# Aux_Power_Board_V2.net
KiCad netlist of a schematic drawn in EAGLE
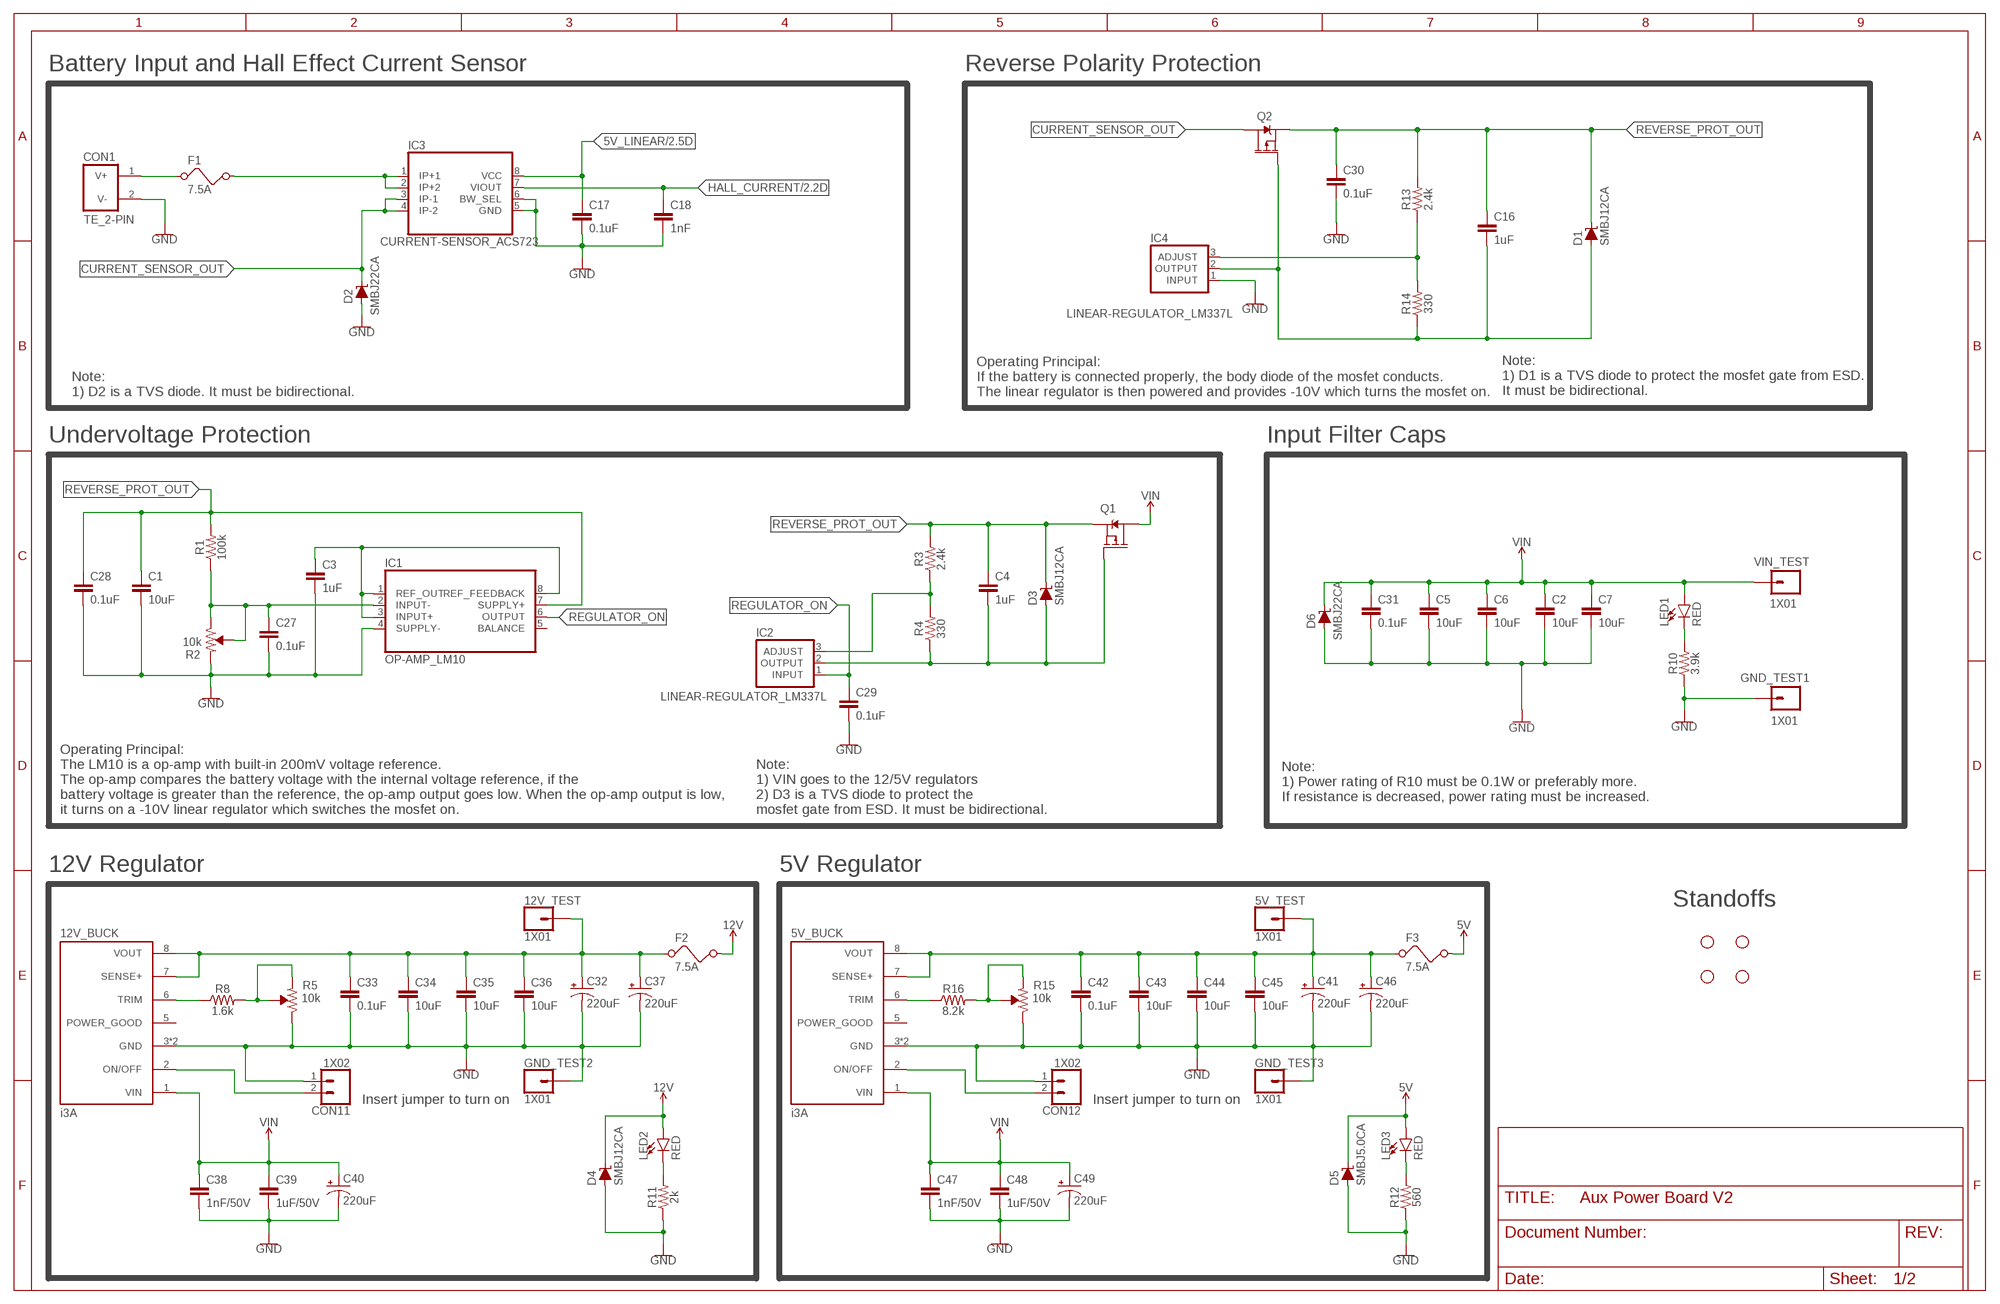
[diagram p0: schematic, sheet 1]
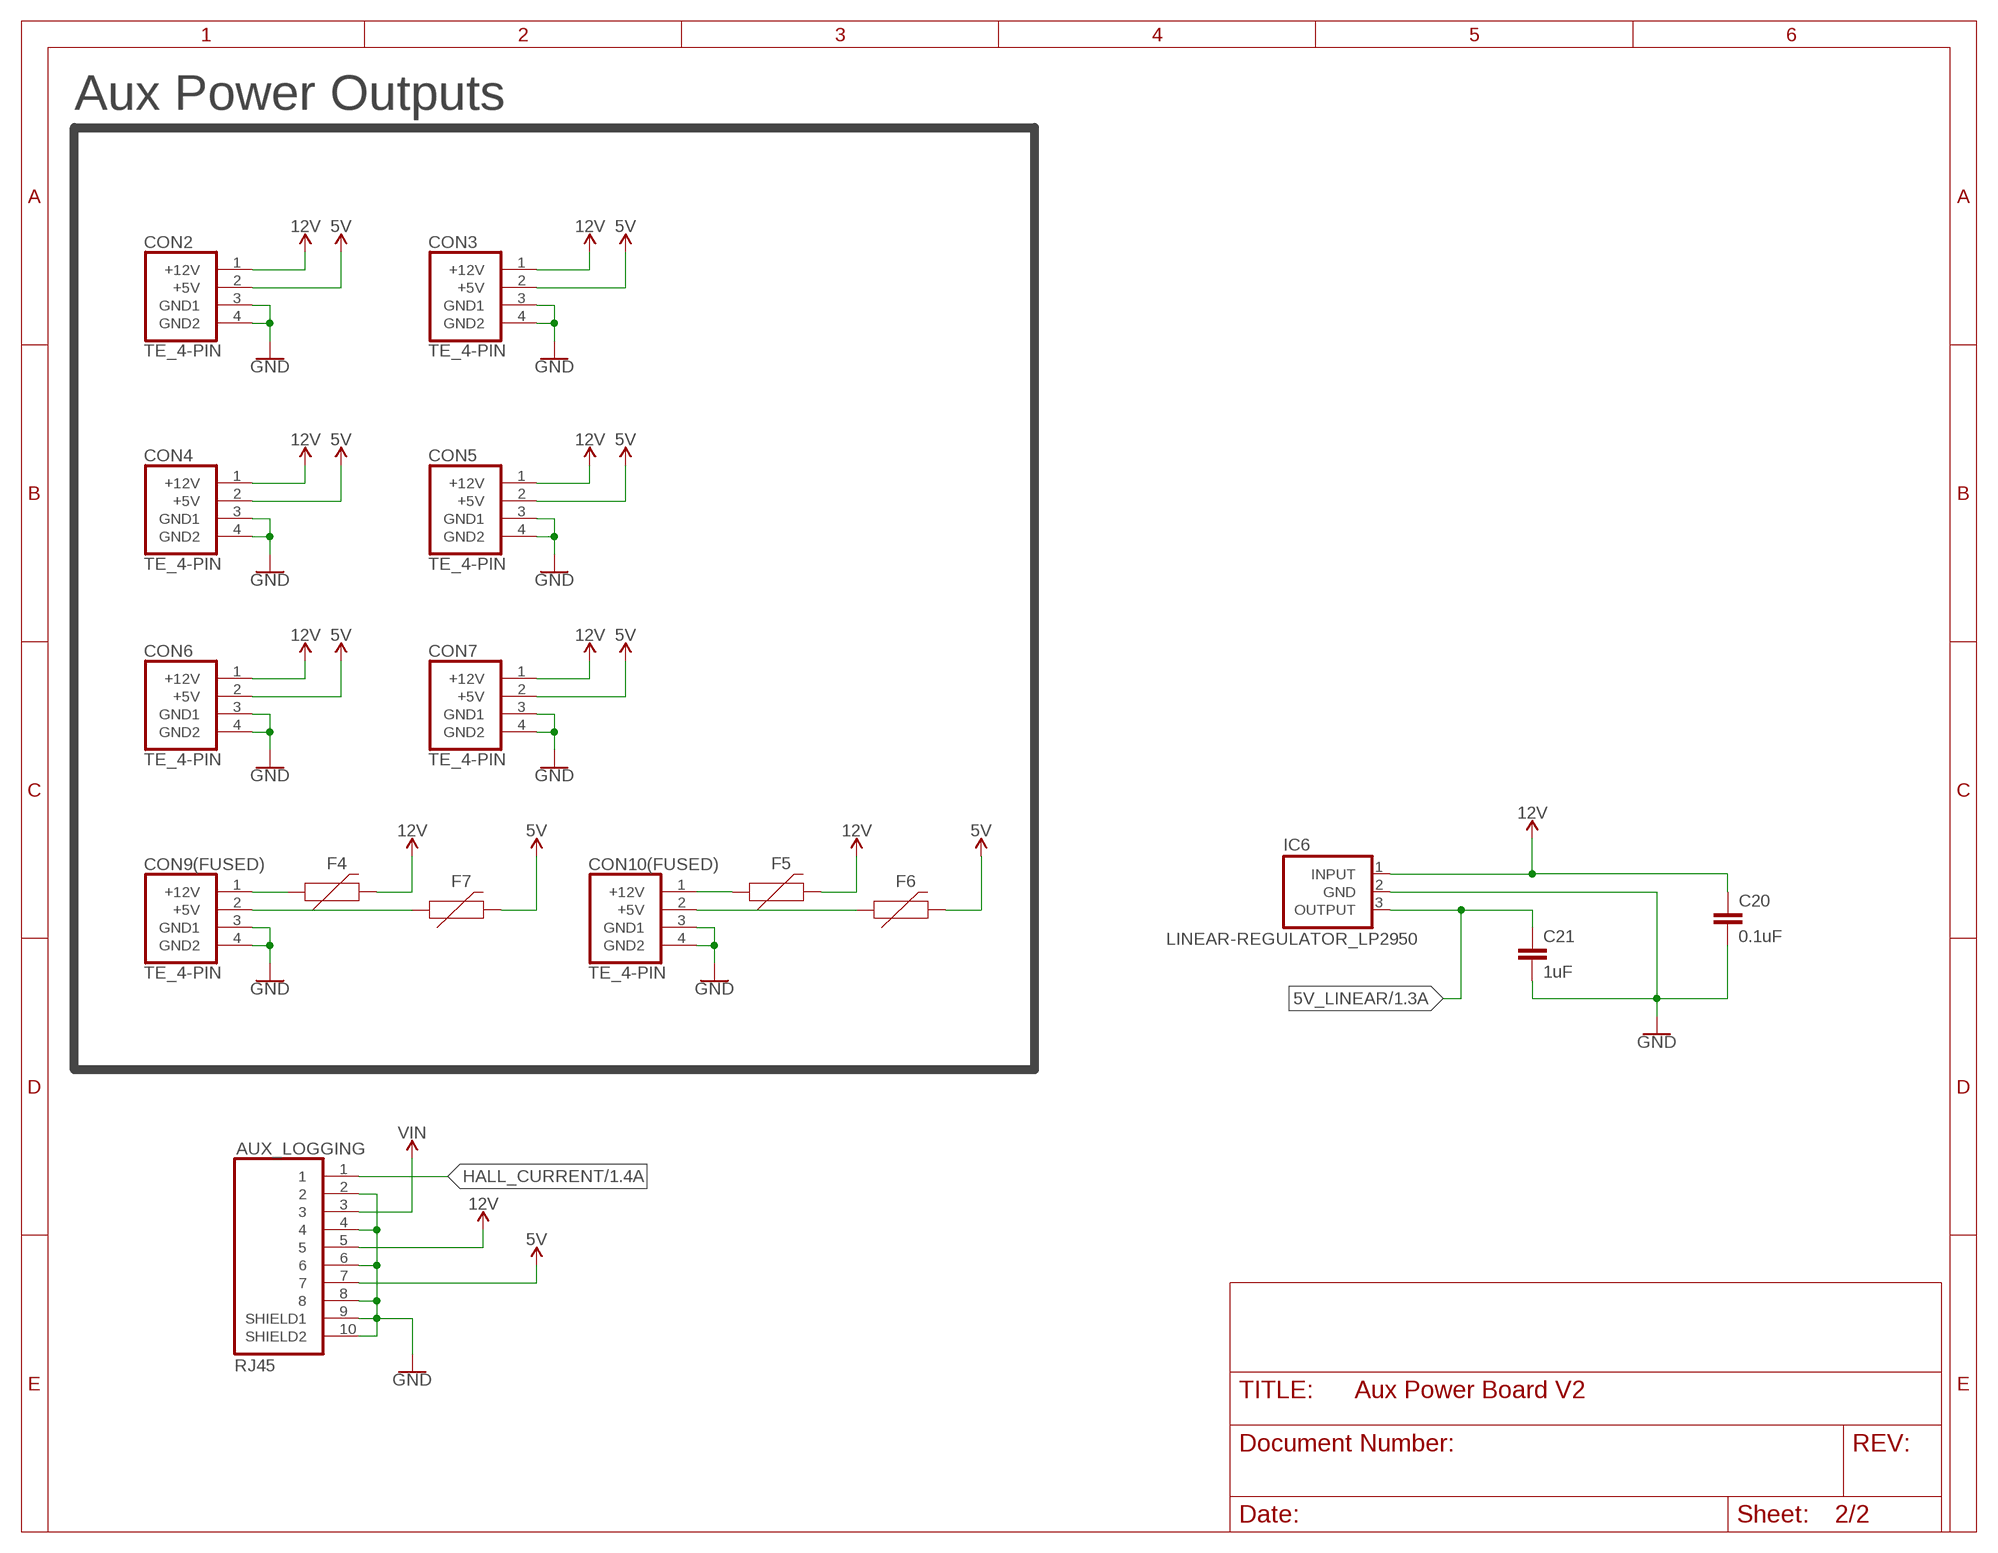
[diagram p1: schematic, sheet 2]

(export (version "E")
  (design (tool "Eeschema 10.0.6"))
  (components
    (comp (ref "AUX_LOGGING")
      (value "RJ45")
      (footprint "eagle-import:RJ45")
      (libsource (lib "eagle-import") (part "RJ45"))
    )
    (comp (ref "C20")
      (value "0.1uF")
      (footprint "eagle-import:0805")
      (libsource (lib "eagle-import") (part "CAPACITOR_0805"))
    )
    (comp (ref "C21")
      (value "1uF")
      (footprint "eagle-import:0805")
      (libsource (lib "eagle-import") (part "CAPACITOR_0805"))
    )
    (comp (ref "CON2")
      (value "TE_4-PIN")
      (footprint "eagle-import:TE_4-PIN")
      (libsource (lib "eagle-import") (part "TE_4-PIN"))
    )
    (comp (ref "CON3")
      (value "TE_4-PIN")
      (footprint "eagle-import:TE_4-PIN")
      (libsource (lib "eagle-import") (part "TE_4-PIN"))
    )
    (comp (ref "CON4")
      (value "TE_4-PIN")
      (footprint "eagle-import:TE_4-PIN")
      (libsource (lib "eagle-import") (part "TE_4-PIN"))
    )
    (comp (ref "CON5")
      (value "TE_4-PIN")
      (footprint "eagle-import:TE_4-PIN")
      (libsource (lib "eagle-import") (part "TE_4-PIN"))
    )
    (comp (ref "CON6")
      (value "TE_4-PIN")
      (footprint "eagle-import:TE_4-PIN")
      (libsource (lib "eagle-import") (part "TE_4-PIN"))
    )
    (comp (ref "CON7")
      (value "TE_4-PIN")
      (footprint "eagle-import:TE_4-PIN")
      (libsource (lib "eagle-import") (part "TE_4-PIN"))
    )
    (comp (ref "CON9(FUSED)")
      (value "TE_4-PIN")
      (footprint "eagle-import:TE_4-PIN")
      (libsource (lib "eagle-import") (part "TE_4-PIN"))
    )
    (comp (ref "CON10(FUSED)")
      (value "TE_4-PIN")
      (footprint "eagle-import:TE_4-PIN")
      (libsource (lib "eagle-import") (part "TE_4-PIN"))
    )
    (comp (ref "F4")
      (value "FUSE_1210_RESETTABLE")
      (footprint "eagle-import:1210")
      (libsource (lib "eagle-import") (part "FUSE_1210_RESETTABLE"))
    )
    (comp (ref "F5")
      (value "FUSE_1210_RESETTABLE")
      (footprint "eagle-import:1210")
      (libsource (lib "eagle-import") (part "FUSE_1210_RESETTABLE"))
    )
    (comp (ref "F6")
      (value "FUSE_1210_RESETTABLE")
      (footprint "eagle-import:1210")
      (libsource (lib "eagle-import") (part "FUSE_1210_RESETTABLE"))
    )
    (comp (ref "F7")
      (value "FUSE_1210_RESETTABLE")
      (footprint "eagle-import:1210")
      (libsource (lib "eagle-import") (part "FUSE_1210_RESETTABLE"))
    )
    (comp (ref "IC6")
      (value "LINEAR-REGULATOR_LP2950")
      (footprint "eagle-import:TO92")
      (libsource (lib "eagle-import") (part "LINEAR-REGULATOR_LP2950"))
    )
    (comp (ref "5V_BUCK")
      (value "i3A")
      (footprint "eagle-import:CONVERTER_I3A")
      (libsource (lib "eagle-import") (part "CONVERTER_I3A"))
    )
    (comp (ref "5V_TEST")
      (value "1X01")
      (footprint "eagle-import:1X01")
      (libsource (lib "eagle-import") (part "1X01"))
    )
    (comp (ref "12V_BUCK")
      (value "i3A")
      (footprint "eagle-import:CONVERTER_I3A")
      (libsource (lib "eagle-import") (part "CONVERTER_I3A"))
    )
    (comp (ref "12V_TEST")
      (value "1X01")
      (footprint "eagle-import:1X01")
      (libsource (lib "eagle-import") (part "1X01"))
    )
    (comp (ref "C1")
      (value "10uF")
      (footprint "eagle-import:1210")
      (libsource (lib "eagle-import") (part "CAPACITOR_1210"))
    )
    (comp (ref "C2")
      (value "10uF")
      (footprint "eagle-import:1210")
      (libsource (lib "eagle-import") (part "CAPACITOR_1210"))
    )
    (comp (ref "C3")
      (value "1uF")
      (footprint "eagle-import:0805")
      (libsource (lib "eagle-import") (part "CAPACITOR_0805"))
    )
    (comp (ref "C4")
      (value "1uF")
      (footprint "eagle-import:0805")
      (libsource (lib "eagle-import") (part "CAPACITOR_0805"))
    )
    (comp (ref "C5")
      (value "10uF")
      (footprint "eagle-import:1210")
      (libsource (lib "eagle-import") (part "CAPACITOR_1210"))
    )
    (comp (ref "C6")
      (value "10uF")
      (footprint "eagle-import:1210")
      (libsource (lib "eagle-import") (part "CAPACITOR_1210"))
    )
    (comp (ref "C7")
      (value "10uF")
      (footprint "eagle-import:1210")
      (libsource (lib "eagle-import") (part "CAPACITOR_1210"))
    )
    (comp (ref "C16")
      (value "1uF")
      (footprint "eagle-import:0805")
      (libsource (lib "eagle-import") (part "CAPACITOR_0805"))
    )
    (comp (ref "C17")
      (value "0.1uF")
      (footprint "eagle-import:0805")
      (libsource (lib "eagle-import") (part "CAPACITOR_0805"))
    )
    (comp (ref "C18")
      (value "1nF")
      (footprint "eagle-import:0805")
      (libsource (lib "eagle-import") (part "CAPACITOR_0805"))
    )
    (comp (ref "C27")
      (value "0.1uF")
      (footprint "eagle-import:0805")
      (libsource (lib "eagle-import") (part "CAPACITOR_0805"))
    )
    (comp (ref "C28")
      (value "0.1uF")
      (footprint "eagle-import:0805")
      (libsource (lib "eagle-import") (part "CAPACITOR_0805"))
    )
    (comp (ref "C29")
      (value "0.1uF")
      (footprint "eagle-import:0805")
      (libsource (lib "eagle-import") (part "CAPACITOR_0805"))
    )
    (comp (ref "C30")
      (value "0.1uF")
      (footprint "eagle-import:0805")
      (libsource (lib "eagle-import") (part "CAPACITOR_0805"))
    )
    (comp (ref "C31")
      (value "0.1uF")
      (footprint "eagle-import:0805")
      (libsource (lib "eagle-import") (part "CAPACITOR_0805"))
    )
    (comp (ref "C32")
      (value "220uF")
      (footprint "eagle-import:CAPACITOR_220UF_63V")
      (libsource (lib "eagle-import") (part "CAPACITOR_ELECTROLYTIC_220UF"))
    )
    (comp (ref "C33")
      (value "0.1uF")
      (footprint "eagle-import:0805")
      (libsource (lib "eagle-import") (part "CAPACITOR_0805"))
    )
    (comp (ref "C34")
      (value "10uF")
      (footprint "eagle-import:0805")
      (libsource (lib "eagle-import") (part "CAPACITOR_0805"))
    )
    (comp (ref "C35")
      (value "10uF")
      (footprint "eagle-import:0805")
      (libsource (lib "eagle-import") (part "CAPACITOR_0805"))
    )
    (comp (ref "C36")
      (value "10uF")
      (footprint "eagle-import:0805")
      (libsource (lib "eagle-import") (part "CAPACITOR_0805"))
    )
    (comp (ref "C37")
      (value "220uF")
      (footprint "eagle-import:CAPACITOR_220UF_63V")
      (libsource (lib "eagle-import") (part "CAPACITOR_ELECTROLYTIC_220UF"))
    )
    (comp (ref "C38")
      (value "1nF/50V")
      (footprint "eagle-import:0805")
      (libsource (lib "eagle-import") (part "CAPACITOR_0805"))
    )
    (comp (ref "C39")
      (value "1uF/50V")
      (footprint "eagle-import:0805")
      (libsource (lib "eagle-import") (part "CAPACITOR_0805"))
    )
    (comp (ref "C40")
      (value "220uF")
      (footprint "eagle-import:CAPACITOR_220UF_63V")
      (libsource (lib "eagle-import") (part "CAPACITOR_ELECTROLYTIC_220UF"))
    )
    (comp (ref "C41")
      (value "220uF")
      (footprint "eagle-import:CAPACITOR_220UF_63V")
      (libsource (lib "eagle-import") (part "CAPACITOR_ELECTROLYTIC_220UF"))
    )
    (comp (ref "C42")
      (value "0.1uF")
      (footprint "eagle-import:0805")
      (libsource (lib "eagle-import") (part "CAPACITOR_0805"))
    )
    (comp (ref "C43")
      (value "10uF")
      (footprint "eagle-import:0805")
      (libsource (lib "eagle-import") (part "CAPACITOR_0805"))
    )
    (comp (ref "C44")
      (value "10uF")
      (footprint "eagle-import:0805")
      (libsource (lib "eagle-import") (part "CAPACITOR_0805"))
    )
    (comp (ref "C45")
      (value "10uF")
      (footprint "eagle-import:0805")
      (libsource (lib "eagle-import") (part "CAPACITOR_0805"))
    )
    (comp (ref "C46")
      (value "220uF")
      (footprint "eagle-import:CAPACITOR_220UF_63V")
      (libsource (lib "eagle-import") (part "CAPACITOR_ELECTROLYTIC_220UF"))
    )
    (comp (ref "C47")
      (value "1nF/50V")
      (footprint "eagle-import:0805")
      (libsource (lib "eagle-import") (part "CAPACITOR_0805"))
    )
    (comp (ref "C48")
      (value "1uF/50V")
      (footprint "eagle-import:0805")
      (libsource (lib "eagle-import") (part "CAPACITOR_0805"))
    )
    (comp (ref "C49")
      (value "220uF")
      (footprint "eagle-import:CAPACITOR_220UF_63V")
      (libsource (lib "eagle-import") (part "CAPACITOR_ELECTROLYTIC_220UF"))
    )
    (comp (ref "CON1")
      (value "TE_2-PIN")
      (footprint "eagle-import:TE_2-PIN")
      (libsource (lib "eagle-import") (part "TE_2-PIN"))
    )
    (comp (ref "CON11")
      (value "1X02")
      (footprint "eagle-import:1X02")
      (libsource (lib "eagle-import") (part "1X02"))
    )
    (comp (ref "CON12")
      (value "1X02")
      (footprint "eagle-import:1X02")
      (libsource (lib "eagle-import") (part "1X02"))
    )
    (comp (ref "D1")
      (value "SMBJ12CA")
      (footprint "eagle-import:DO214AA")
      (libsource (lib "eagle-import") (part "DIODE_TVS_DO-214AA"))
    )
    (comp (ref "D2")
      (value "SMBJ22CA")
      (footprint "eagle-import:DO214AA")
      (libsource (lib "eagle-import") (part "DIODE_TVS_DO-214AA"))
    )
    (comp (ref "D3")
      (value "SMBJ12CA")
      (footprint "eagle-import:DO214AA")
      (libsource (lib "eagle-import") (part "DIODE_TVS_DO-214AA"))
    )
    (comp (ref "D4")
      (value "SMBJ12CA")
      (footprint "eagle-import:DO214AA")
      (libsource (lib "eagle-import") (part "DIODE_TVS_DO-214AA"))
    )
    (comp (ref "D5")
      (value "SMBJ5.0CA")
      (footprint "eagle-import:DO214AA")
      (libsource (lib "eagle-import") (part "DIODE_TVS_DO-214AA"))
    )
    (comp (ref "D6")
      (value "SMBJ22CA")
      (footprint "eagle-import:DO214AA")
      (libsource (lib "eagle-import") (part "DIODE_TVS_DO-214AA"))
    )
    (comp (ref "F1")
      (value "7.5A")
      (footprint "eagle-import:FUSEHOLDER_VERTICAL")
      (libsource (lib "eagle-import") (part "FUSEHOLDER_VERTICAL"))
    )
    (comp (ref "F2")
      (value "7.5A")
      (footprint "eagle-import:FUSEHOLDER_VERTICAL")
      (libsource (lib "eagle-import") (part "FUSEHOLDER_VERTICAL"))
    )
    (comp (ref "F3")
      (value "7.5A")
      (footprint "eagle-import:FUSEHOLDER_VERTICAL")
      (libsource (lib "eagle-import") (part "FUSEHOLDER_VERTICAL"))
    )
    (comp (ref "GND_TEST1")
      (value "1X01")
      (footprint "eagle-import:1X01")
      (libsource (lib "eagle-import") (part "1X01"))
    )
    (comp (ref "GND_TEST2")
      (value "1X01")
      (footprint "eagle-import:1X01")
      (libsource (lib "eagle-import") (part "1X01"))
    )
    (comp (ref "GND_TEST3")
      (value "1X01")
      (footprint "eagle-import:1X01")
      (libsource (lib "eagle-import") (part "1X01"))
    )
    (comp (ref "H1")
      (value "STAND-OFF")
      (footprint "eagle-import:STAND-OFF")
      (libsource (lib "eagle-import") (part "STAND-OFF"))
    )
    (comp (ref "H2")
      (value "STAND-OFF")
      (footprint "eagle-import:STAND-OFF")
      (libsource (lib "eagle-import") (part "STAND-OFF"))
    )
    (comp (ref "H3")
      (value "STAND-OFF")
      (footprint "eagle-import:STAND-OFF")
      (libsource (lib "eagle-import") (part "STAND-OFF"))
    )
    (comp (ref "H4")
      (value "STAND-OFF")
      (footprint "eagle-import:STAND-OFF")
      (libsource (lib "eagle-import") (part "STAND-OFF"))
    )
    (comp (ref "IC1")
      (value "OP-AMP_LM10")
      (footprint "eagle-import:DIP08")
      (libsource (lib "eagle-import") (part "OP-AMP_LM10"))
    )
    (comp (ref "IC2")
      (value "LINEAR-REGULATOR_LM337L")
      (footprint "eagle-import:TO92")
      (libsource (lib "eagle-import") (part "LINEAR-REGULATOR_LM337L"))
    )
    (comp (ref "IC3")
      (value "CURRENT-SENSOR_ACS723")
      (footprint "eagle-import:SOIC8")
      (libsource (lib "eagle-import") (part "CURRENT-SENSOR_ACS723"))
    )
    (comp (ref "IC4")
      (value "LINEAR-REGULATOR_LM337L")
      (footprint "eagle-import:TO92")
      (libsource (lib "eagle-import") (part "LINEAR-REGULATOR_LM337L"))
    )
    (comp (ref "LED1")
      (value "RED")
      (footprint "eagle-import:0805_LED")
      (libsource (lib "eagle-import") (part "LED_0805"))
    )
    (comp (ref "LED2")
      (value "RED")
      (footprint "eagle-import:0805_LED")
      (libsource (lib "eagle-import") (part "LED_0805"))
    )
    (comp (ref "LED3")
      (value "RED")
      (footprint "eagle-import:0805_LED")
      (libsource (lib "eagle-import") (part "LED_0805"))
    )
    (comp (ref "Q1")
      (value "MOSFET_PMOS_TO-263")
      (footprint "eagle-import:TO-263_D2PAK")
      (libsource (lib "eagle-import") (part "MOSFET_PMOS_TO-263"))
    )
    (comp (ref "Q2")
      (value "MOSFET_PMOS_TO-263")
      (footprint "eagle-import:TO-263_D2PAK")
      (libsource (lib "eagle-import") (part "MOSFET_PMOS_TO-263"))
    )
    (comp (ref "R1")
      (value "100k")
      (footprint "eagle-import:0805")
      (libsource (lib "eagle-import") (part "RESISTOR_0805"))
    )
    (comp (ref "R2")
      (value "10k")
      (footprint "eagle-import:TRIMPOT")
      (libsource (lib "eagle-import") (part "RESISTOR_TRIMPOT"))
    )
    (comp (ref "R3")
      (value "2.4k")
      (footprint "eagle-import:0805")
      (libsource (lib "eagle-import") (part "RESISTOR_0805"))
    )
    (comp (ref "R4")
      (value "330")
      (footprint "eagle-import:0805")
      (libsource (lib "eagle-import") (part "RESISTOR_0805"))
    )
    (comp (ref "R5")
      (value "10k")
      (footprint "eagle-import:TRIMPOT")
      (libsource (lib "eagle-import") (part "RESISTOR_TRIMPOT"))
    )
    (comp (ref "R8")
      (value "1.6k")
      (footprint "eagle-import:0805")
      (libsource (lib "eagle-import") (part "RESISTOR_0805"))
    )
    (comp (ref "R10")
      (value "3.9k")
      (footprint "eagle-import:0805")
      (libsource (lib "eagle-import") (part "RESISTOR_0805"))
    )
    (comp (ref "R11")
      (value "2k")
      (footprint "eagle-import:0805")
      (libsource (lib "eagle-import") (part "RESISTOR_0805"))
    )
    (comp (ref "R12")
      (value "560")
      (footprint "eagle-import:0805")
      (libsource (lib "eagle-import") (part "RESISTOR_0805"))
    )
    (comp (ref "R13")
      (value "2.4k")
      (footprint "eagle-import:0805")
      (libsource (lib "eagle-import") (part "RESISTOR_0805"))
    )
    (comp (ref "R14")
      (value "330")
      (footprint "eagle-import:0805")
      (libsource (lib "eagle-import") (part "RESISTOR_0805"))
    )
    (comp (ref "R15")
      (value "10k")
      (footprint "eagle-import:TRIMPOT")
      (libsource (lib "eagle-import") (part "RESISTOR_TRIMPOT"))
    )
    (comp (ref "R16")
      (value "8.2k")
      (footprint "eagle-import:0805")
      (libsource (lib "eagle-import") (part "RESISTOR_0805"))
    )
    (comp (ref "VIN_TEST")
      (value "1X01")
      (footprint "eagle-import:1X01")
      (libsource (lib "eagle-import") (part "1X01"))
    )
  )
  (nets
    (net (code "1") (name "5V") (class "Default")
      (node (ref "AUX_LOGGING") (pin "7") (pinfunction "7_7") (pintype "passive"))
      (node (ref "CON2") (pin "2") (pinfunction "+5V_2") (pintype "passive"))
      (node (ref "CON3") (pin "2") (pinfunction "+5V_2") (pintype "passive"))
      (node (ref "CON4") (pin "2") (pinfunction "+5V_2") (pintype "passive"))
      (node (ref "CON5") (pin "2") (pinfunction "+5V_2") (pintype "passive"))
      (node (ref "CON6") (pin "2") (pinfunction "+5V_2") (pintype "passive"))
      (node (ref "CON7") (pin "2") (pinfunction "+5V_2") (pintype "passive"))
      (node (ref "D5") (pin "C") (pinfunction "C_C") (pintype "passive"))
      (node (ref "F3") (pin "3") (pinfunction "2_3") (pintype "passive"))
      (node (ref "F3") (pin "4") (pinfunction "2_4") (pintype "passive"))
      (node (ref "F6") (pin "2") (pinfunction "2_2") (pintype "bidirectional"))
      (node (ref "F7") (pin "2") (pinfunction "2_2") (pintype "bidirectional"))
      (node (ref "LED3") (pin "1") (pinfunction "A_1") (pintype "passive"))
    )
    (net (code "2") (name "5V_LINEAR") (class "Default")
      (node (ref "C17") (pin "1") (pinfunction "1_1") (pintype "passive"))
      (node (ref "C21") (pin "1") (pinfunction "1_1") (pintype "passive"))
      (node (ref "IC3") (pin "8") (pinfunction "VCC_8") (pintype "bidirectional"))
      (node (ref "IC6") (pin "3") (pinfunction "OUTPUT_3") (pintype "bidirectional"))
    )
    (net (code "3") (name "12V") (class "Default")
      (node (ref "AUX_LOGGING") (pin "5") (pinfunction "5_5") (pintype "passive"))
      (node (ref "C20") (pin "1") (pinfunction "1_1") (pintype "passive"))
      (node (ref "CON2") (pin "1") (pinfunction "+12V_1") (pintype "passive"))
      (node (ref "CON3") (pin "1") (pinfunction "+12V_1") (pintype "passive"))
      (node (ref "CON4") (pin "1") (pinfunction "+12V_1") (pintype "passive"))
      (node (ref "CON5") (pin "1") (pinfunction "+12V_1") (pintype "passive"))
      (node (ref "CON6") (pin "1") (pinfunction "+12V_1") (pintype "passive"))
      (node (ref "CON7") (pin "1") (pinfunction "+12V_1") (pintype "passive"))
      (node (ref "D4") (pin "C") (pinfunction "C_C") (pintype "passive"))
      (node (ref "F2") (pin "3") (pinfunction "2_3") (pintype "passive"))
      (node (ref "F2") (pin "4") (pinfunction "2_4") (pintype "passive"))
      (node (ref "F4") (pin "2") (pinfunction "2_2") (pintype "bidirectional"))
      (node (ref "F5") (pin "2") (pinfunction "2_2") (pintype "bidirectional"))
      (node (ref "IC6") (pin "1") (pinfunction "INPUT_1") (pintype "bidirectional"))
      (node (ref "LED2") (pin "1") (pinfunction "A_1") (pintype "passive"))
    )
    (net (code "4") (name "CURRENT_SENSOR_OUT") (class "Default")
      (node (ref "D2") (pin "C") (pinfunction "C_C") (pintype "passive"))
      (node (ref "IC3") (pin "3") (pinfunction "IP-1_3") (pintype "bidirectional"))
      (node (ref "IC3") (pin "4") (pinfunction "IP-2_4") (pintype "bidirectional"))
      (node (ref "Q2") (pin "2") (pinfunction "D_2") (pintype "bidirectional"))
    )
    (net (code "5") (name "GND") (class "Default")
      (node (ref "12V_BUCK") (pin "3") (pinfunction "GND_3") (pintype "bidirectional"))
      (node (ref "12V_BUCK") (pin "4") (pinfunction "GND_4") (pintype "bidirectional"))
      (node (ref "5V_BUCK") (pin "3") (pinfunction "GND_3") (pintype "bidirectional"))
      (node (ref "5V_BUCK") (pin "4") (pinfunction "GND_4") (pintype "bidirectional"))
      (node (ref "AUX_LOGGING") (pin "10") (pinfunction "SHIELD2_10") (pintype "passive"))
      (node (ref "AUX_LOGGING") (pin "2") (pinfunction "2_2") (pintype "passive"))
      (node (ref "AUX_LOGGING") (pin "4") (pinfunction "4_4") (pintype "passive"))
      (node (ref "AUX_LOGGING") (pin "6") (pinfunction "6_6") (pintype "passive"))
      (node (ref "AUX_LOGGING") (pin "8") (pinfunction "8_8") (pintype "passive"))
      (node (ref "AUX_LOGGING") (pin "9") (pinfunction "SHIELD1_9") (pintype "passive"))
      (node (ref "C1") (pin "2") (pinfunction "2_2") (pintype "passive"))
      (node (ref "C17") (pin "2") (pinfunction "2_2") (pintype "passive"))
      (node (ref "C18") (pin "2") (pinfunction "2_2") (pintype "passive"))
      (node (ref "C2") (pin "2") (pinfunction "2_2") (pintype "passive"))
      (node (ref "C20") (pin "2") (pinfunction "2_2") (pintype "passive"))
      (node (ref "C21") (pin "2") (pinfunction "2_2") (pintype "passive"))
      (node (ref "C27") (pin "2") (pinfunction "2_2") (pintype "passive"))
      (node (ref "C28") (pin "2") (pinfunction "2_2") (pintype "passive"))
      (node (ref "C29") (pin "2") (pinfunction "2_2") (pintype "passive"))
      (node (ref "C3") (pin "2") (pinfunction "2_2") (pintype "passive"))
      (node (ref "C30") (pin "2") (pinfunction "2_2") (pintype "passive"))
      (node (ref "C31") (pin "2") (pinfunction "2_2") (pintype "passive"))
      (node (ref "C32") (pin "-") (pinfunction "-_-") (pintype "passive"))
      (node (ref "C33") (pin "2") (pinfunction "2_2") (pintype "passive"))
      (node (ref "C34") (pin "2") (pinfunction "2_2") (pintype "passive"))
      (node (ref "C35") (pin "2") (pinfunction "2_2") (pintype "passive"))
      (node (ref "C36") (pin "2") (pinfunction "2_2") (pintype "passive"))
      (node (ref "C37") (pin "-") (pinfunction "-_-") (pintype "passive"))
      (node (ref "C38") (pin "2") (pinfunction "2_2") (pintype "passive"))
      (node (ref "C39") (pin "2") (pinfunction "2_2") (pintype "passive"))
      (node (ref "C40") (pin "-") (pinfunction "-_-") (pintype "passive"))
      (node (ref "C41") (pin "-") (pinfunction "-_-") (pintype "passive"))
      (node (ref "C42") (pin "2") (pinfunction "2_2") (pintype "passive"))
      (node (ref "C43") (pin "2") (pinfunction "2_2") (pintype "passive"))
      (node (ref "C44") (pin "2") (pinfunction "2_2") (pintype "passive"))
      (node (ref "C45") (pin "2") (pinfunction "2_2") (pintype "passive"))
      (node (ref "C46") (pin "-") (pinfunction "-_-") (pintype "passive"))
      (node (ref "C47") (pin "2") (pinfunction "2_2") (pintype "passive"))
      (node (ref "C48") (pin "2") (pinfunction "2_2") (pintype "passive"))
      (node (ref "C49") (pin "-") (pinfunction "-_-") (pintype "passive"))
      (node (ref "C5") (pin "2") (pinfunction "2_2") (pintype "passive"))
      (node (ref "C6") (pin "2") (pinfunction "2_2") (pintype "passive"))
      (node (ref "C7") (pin "2") (pinfunction "2_2") (pintype "passive"))
      (node (ref "CON1") (pin "2") (pinfunction "V-_2") (pintype "passive"))
      (node (ref "CON10(FUSED)") (pin "3") (pinfunction "GND1_3") (pintype "passive"))
      (node (ref "CON10(FUSED)") (pin "4") (pinfunction "GND2_4") (pintype "passive"))
      (node (ref "CON11") (pin "1") (pinfunction "1_1") (pintype "passive"))
      (node (ref "CON12") (pin "1") (pinfunction "1_1") (pintype "passive"))
      (node (ref "CON2") (pin "3") (pinfunction "GND1_3") (pintype "passive"))
      (node (ref "CON2") (pin "4") (pinfunction "GND2_4") (pintype "passive"))
      (node (ref "CON3") (pin "3") (pinfunction "GND1_3") (pintype "passive"))
      (node (ref "CON3") (pin "4") (pinfunction "GND2_4") (pintype "passive"))
      (node (ref "CON4") (pin "3") (pinfunction "GND1_3") (pintype "passive"))
      (node (ref "CON4") (pin "4") (pinfunction "GND2_4") (pintype "passive"))
      (node (ref "CON5") (pin "3") (pinfunction "GND1_3") (pintype "passive"))
      (node (ref "CON5") (pin "4") (pinfunction "GND2_4") (pintype "passive"))
      (node (ref "CON6") (pin "3") (pinfunction "GND1_3") (pintype "passive"))
      (node (ref "CON6") (pin "4") (pinfunction "GND2_4") (pintype "passive"))
      (node (ref "CON7") (pin "3") (pinfunction "GND1_3") (pintype "passive"))
      (node (ref "CON7") (pin "4") (pinfunction "GND2_4") (pintype "passive"))
      (node (ref "CON9(FUSED)") (pin "3") (pinfunction "GND1_3") (pintype "passive"))
      (node (ref "CON9(FUSED)") (pin "4") (pinfunction "GND2_4") (pintype "passive"))
      (node (ref "D2") (pin "A") (pinfunction "A_A") (pintype "passive"))
      (node (ref "D4") (pin "A") (pinfunction "A_A") (pintype "passive"))
      (node (ref "D5") (pin "A") (pinfunction "A_A") (pintype "passive"))
      (node (ref "D6") (pin "A") (pinfunction "A_A") (pintype "passive"))
      (node (ref "GND_TEST1") (pin "1") (pinfunction "1_1") (pintype "passive"))
      (node (ref "GND_TEST2") (pin "1") (pinfunction "1_1") (pintype "passive"))
      (node (ref "GND_TEST3") (pin "1") (pinfunction "1_1") (pintype "passive"))
      (node (ref "IC1") (pin "4") (pinfunction "SUPPLY-_4") (pintype "bidirectional"))
      (node (ref "IC3") (pin "5") (pinfunction "GND_5") (pintype "bidirectional"))
      (node (ref "IC3") (pin "6") (pinfunction "BW_SEL_6") (pintype "bidirectional"))
      (node (ref "IC4") (pin "1") (pinfunction "INPUT_1") (pintype "bidirectional"))
      (node (ref "IC6") (pin "2") (pinfunction "GND_2") (pintype "bidirectional"))
      (node (ref "R10") (pin "1") (pinfunction "1_1") (pintype "passive"))
      (node (ref "R11") (pin "1") (pinfunction "1_1") (pintype "passive"))
      (node (ref "R12") (pin "1") (pinfunction "1_1") (pintype "passive"))
      (node (ref "R15") (pin "3") (pinfunction "CW_3") (pintype "passive"))
      (node (ref "R2") (pin "1") (pinfunction "CCW_1") (pintype "passive"))
      (node (ref "R5") (pin "3") (pinfunction "CW_3") (pintype "passive"))
    )
    (net (code "6") (name "HALL_CURRENT") (class "Default")
      (node (ref "AUX_LOGGING") (pin "1") (pinfunction "1_1") (pintype "passive"))
      (node (ref "C18") (pin "1") (pinfunction "1_1") (pintype "passive"))
      (node (ref "IC3") (pin "7") (pinfunction "VIOUT_7") (pintype "bidirectional"))
    )
    (net (code "7") (name "Net-(5V_BUCK-ON{slash}OFF)") (class "Default")
      (node (ref "5V_BUCK") (pin "2") (pinfunction "ON/OFF_2") (pintype "bidirectional"))
      (node (ref "CON12") (pin "2") (pinfunction "2_2") (pintype "passive"))
    )
    (net (code "8") (name "Net-(5V_BUCK-SENSE+)") (class "Default")
      (node (ref "5V_BUCK") (pin "7") (pinfunction "SENSE+_7") (pintype "bidirectional"))
      (node (ref "5V_BUCK") (pin "8") (pinfunction "VOUT_8") (pintype "bidirectional"))
      (node (ref "5V_TEST") (pin "1") (pinfunction "1_1") (pintype "passive"))
      (node (ref "C41") (pin "+") (pinfunction "+_+") (pintype "passive"))
      (node (ref "C42") (pin "1") (pinfunction "1_1") (pintype "passive"))
      (node (ref "C43") (pin "1") (pinfunction "1_1") (pintype "passive"))
      (node (ref "C44") (pin "1") (pinfunction "1_1") (pintype "passive"))
      (node (ref "C45") (pin "1") (pinfunction "1_1") (pintype "passive"))
      (node (ref "C46") (pin "+") (pinfunction "+_+") (pintype "passive"))
      (node (ref "F3") (pin "1") (pinfunction "1_1") (pintype "passive"))
      (node (ref "F3") (pin "2") (pinfunction "1_2") (pintype "passive"))
    )
    (net (code "9") (name "Net-(5V_BUCK-TRIM)") (class "Default")
      (node (ref "5V_BUCK") (pin "6") (pinfunction "TRIM_6") (pintype "bidirectional"))
      (node (ref "R16") (pin "1") (pinfunction "1_1") (pintype "passive"))
    )
    (net (code "10") (name "Net-(12V_BUCK-ON{slash}OFF)") (class "Default")
      (node (ref "12V_BUCK") (pin "2") (pinfunction "ON/OFF_2") (pintype "bidirectional"))
      (node (ref "CON11") (pin "2") (pinfunction "2_2") (pintype "passive"))
    )
    (net (code "11") (name "Net-(12V_BUCK-SENSE+)") (class "Default")
      (node (ref "12V_BUCK") (pin "7") (pinfunction "SENSE+_7") (pintype "bidirectional"))
      (node (ref "12V_BUCK") (pin "8") (pinfunction "VOUT_8") (pintype "bidirectional"))
      (node (ref "12V_TEST") (pin "1") (pinfunction "1_1") (pintype "passive"))
      (node (ref "C32") (pin "+") (pinfunction "+_+") (pintype "passive"))
      (node (ref "C33") (pin "1") (pinfunction "1_1") (pintype "passive"))
      (node (ref "C34") (pin "1") (pinfunction "1_1") (pintype "passive"))
      (node (ref "C35") (pin "1") (pinfunction "1_1") (pintype "passive"))
      (node (ref "C36") (pin "1") (pinfunction "1_1") (pintype "passive"))
      (node (ref "C37") (pin "+") (pinfunction "+_+") (pintype "passive"))
      (node (ref "F2") (pin "1") (pinfunction "1_1") (pintype "passive"))
      (node (ref "F2") (pin "2") (pinfunction "1_2") (pintype "passive"))
    )
    (net (code "12") (name "Net-(12V_BUCK-TRIM)") (class "Default")
      (node (ref "12V_BUCK") (pin "6") (pinfunction "TRIM_6") (pintype "bidirectional"))
      (node (ref "R8") (pin "1") (pinfunction "1_1") (pintype "passive"))
    )
    (net (code "13") (name "Net-(CON1-V+)") (class "Default")
      (node (ref "CON1") (pin "1") (pinfunction "V+_1") (pintype "passive"))
      (node (ref "F1") (pin "1") (pinfunction "1_1") (pintype "passive"))
      (node (ref "F1") (pin "2") (pinfunction "1_2") (pintype "passive"))
    )
    (net (code "14") (name "Net-(CON9(FUSED)-+5V)") (class "Default")
      (node (ref "CON9(FUSED)") (pin "2") (pinfunction "+5V_2") (pintype "passive"))
      (node (ref "F7") (pin "1") (pinfunction "1_1") (pintype "bidirectional"))
    )
    (net (code "15") (name "Net-(CON9(FUSED)-+12V)") (class "Default")
      (node (ref "CON9(FUSED)") (pin "1") (pinfunction "+12V_1") (pintype "passive"))
      (node (ref "F4") (pin "1") (pinfunction "1_1") (pintype "bidirectional"))
    )
    (net (code "16") (name "Net-(CON10(FUSED)-+5V)") (class "Default")
      (node (ref "CON10(FUSED)") (pin "2") (pinfunction "+5V_2") (pintype "passive"))
      (node (ref "F6") (pin "1") (pinfunction "1_1") (pintype "bidirectional"))
    )
    (net (code "17") (name "Net-(CON10(FUSED)-+12V)") (class "Default")
      (node (ref "CON10(FUSED)") (pin "1") (pinfunction "+12V_1") (pintype "passive"))
      (node (ref "F5") (pin "1") (pinfunction "1_1") (pintype "bidirectional"))
    )
    (net (code "18") (name "Net-(IC1-INPUT+)") (class "Default")
      (node (ref "C3") (pin "1") (pinfunction "1_1") (pintype "passive"))
      (node (ref "IC1") (pin "1") (pinfunction "REF_OUT_1") (pintype "bidirectional"))
      (node (ref "IC1") (pin "3") (pinfunction "INPUT+_3") (pintype "bidirectional"))
      (node (ref "IC1") (pin "8") (pinfunction "REF_FEEDBACK_8") (pintype "bidirectional"))
    )
    (net (code "19") (name "Net-(IC1-INPUT-)") (class "Default")
      (node (ref "C27") (pin "1") (pinfunction "1_1") (pintype "passive"))
      (node (ref "IC1") (pin "2") (pinfunction "INPUT-_2") (pintype "bidirectional"))
      (node (ref "R1") (pin "1") (pinfunction "1_1") (pintype "passive"))
      (node (ref "R2") (pin "2") (pinfunction "WIPER_2") (pintype "passive"))
      (node (ref "R2") (pin "3") (pinfunction "CW_3") (pintype "passive"))
    )
    (net (code "20") (name "Net-(IC2-ADJUST)") (class "Default")
      (node (ref "IC2") (pin "3") (pinfunction "ADJUST_3") (pintype "bidirectional"))
      (node (ref "R3") (pin "1") (pinfunction "1_1") (pintype "passive"))
      (node (ref "R4") (pin "2") (pinfunction "2_2") (pintype "passive"))
    )
    (net (code "21") (name "Net-(IC2-OUTPUT)") (class "Default")
      (node (ref "C4") (pin "2") (pinfunction "2_2") (pintype "passive"))
      (node (ref "D3") (pin "A") (pinfunction "A_A") (pintype "passive"))
      (node (ref "IC2") (pin "2") (pinfunction "OUTPUT_2") (pintype "bidirectional"))
      (node (ref "Q1") (pin "1") (pinfunction "G_1") (pintype "bidirectional"))
      (node (ref "R4") (pin "1") (pinfunction "1_1") (pintype "passive"))
    )
    (net (code "22") (name "Net-(IC3-IP+1)") (class "Default")
      (node (ref "F1") (pin "3") (pinfunction "2_3") (pintype "passive"))
      (node (ref "F1") (pin "4") (pinfunction "2_4") (pintype "passive"))
      (node (ref "IC3") (pin "1") (pinfunction "IP+1_1") (pintype "bidirectional"))
      (node (ref "IC3") (pin "2") (pinfunction "IP+2_2") (pintype "bidirectional"))
    )
    (net (code "23") (name "Net-(IC4-ADJUST)") (class "Default")
      (node (ref "IC4") (pin "3") (pinfunction "ADJUST_3") (pintype "bidirectional"))
      (node (ref "R13") (pin "1") (pinfunction "1_1") (pintype "passive"))
      (node (ref "R14") (pin "2") (pinfunction "2_2") (pintype "passive"))
    )
    (net (code "24") (name "Net-(IC4-OUTPUT)") (class "Default")
      (node (ref "C16") (pin "2") (pinfunction "2_2") (pintype "passive"))
      (node (ref "D1") (pin "A") (pinfunction "A_A") (pintype "passive"))
      (node (ref "IC4") (pin "2") (pinfunction "OUTPUT_2") (pintype "bidirectional"))
      (node (ref "Q2") (pin "1") (pinfunction "G_1") (pintype "bidirectional"))
      (node (ref "R14") (pin "1") (pinfunction "1_1") (pintype "passive"))
    )
    (net (code "25") (name "Net-(LED1-C)") (class "Default")
      (node (ref "LED1") (pin "2") (pinfunction "C_2") (pintype "passive"))
      (node (ref "R10") (pin "2") (pinfunction "2_2") (pintype "passive"))
    )
    (net (code "26") (name "Net-(LED2-C)") (class "Default")
      (node (ref "LED2") (pin "2") (pinfunction "C_2") (pintype "passive"))
      (node (ref "R11") (pin "2") (pinfunction "2_2") (pintype "passive"))
    )
    (net (code "27") (name "Net-(LED3-C)") (class "Default")
      (node (ref "LED3") (pin "2") (pinfunction "C_2") (pintype "passive"))
      (node (ref "R12") (pin "2") (pinfunction "2_2") (pintype "passive"))
    )
    (net (code "28") (name "Net-(R5-CCW)") (class "Default")
      (node (ref "R5") (pin "1") (pinfunction "CCW_1") (pintype "passive"))
      (node (ref "R5") (pin "2") (pinfunction "WIPER_2") (pintype "passive"))
      (node (ref "R8") (pin "2") (pinfunction "2_2") (pintype "passive"))
    )
    (net (code "29") (name "Net-(R15-CCW)") (class "Default")
      (node (ref "R15") (pin "1") (pinfunction "CCW_1") (pintype "passive"))
      (node (ref "R15") (pin "2") (pinfunction "WIPER_2") (pintype "passive"))
      (node (ref "R16") (pin "2") (pinfunction "2_2") (pintype "passive"))
    )
    (net (code "30") (name "REGULATOR_ON") (class "Default")
      (node (ref "C29") (pin "1") (pinfunction "1_1") (pintype "passive"))
      (node (ref "IC1") (pin "6") (pinfunction "OUTPUT_6") (pintype "bidirectional"))
      (node (ref "IC2") (pin "1") (pinfunction "INPUT_1") (pintype "bidirectional"))
    )
    (net (code "31") (name "REVERSE_PROT_OUT") (class "Default")
      (node (ref "C1") (pin "1") (pinfunction "1_1") (pintype "passive"))
      (node (ref "C16") (pin "1") (pinfunction "1_1") (pintype "passive"))
      (node (ref "C28") (pin "1") (pinfunction "1_1") (pintype "passive"))
      (node (ref "C30") (pin "1") (pinfunction "1_1") (pintype "passive"))
      (node (ref "C4") (pin "1") (pinfunction "1_1") (pintype "passive"))
      (node (ref "D1") (pin "C") (pinfunction "C_C") (pintype "passive"))
      (node (ref "D3") (pin "C") (pinfunction "C_C") (pintype "passive"))
      (node (ref "IC1") (pin "7") (pinfunction "SUPPLY+_7") (pintype "bidirectional"))
      (node (ref "Q1") (pin "3") (pinfunction "S_3") (pintype "bidirectional"))
      (node (ref "Q2") (pin "3") (pinfunction "S_3") (pintype "bidirectional"))
      (node (ref "R1") (pin "2") (pinfunction "2_2") (pintype "passive"))
      (node (ref "R13") (pin "2") (pinfunction "2_2") (pintype "passive"))
      (node (ref "R3") (pin "2") (pinfunction "2_2") (pintype "passive"))
    )
    (net (code "32") (name "VIN") (class "Default")
      (node (ref "12V_BUCK") (pin "1") (pinfunction "VIN_1") (pintype "bidirectional"))
      (node (ref "5V_BUCK") (pin "1") (pinfunction "VIN_1") (pintype "bidirectional"))
      (node (ref "AUX_LOGGING") (pin "3") (pinfunction "3_3") (pintype "passive"))
      (node (ref "C2") (pin "1") (pinfunction "1_1") (pintype "passive"))
      (node (ref "C31") (pin "1") (pinfunction "1_1") (pintype "passive"))
      (node (ref "C38") (pin "1") (pinfunction "1_1") (pintype "passive"))
      (node (ref "C39") (pin "1") (pinfunction "1_1") (pintype "passive"))
      (node (ref "C40") (pin "+") (pinfunction "+_+") (pintype "passive"))
      (node (ref "C47") (pin "1") (pinfunction "1_1") (pintype "passive"))
      (node (ref "C48") (pin "1") (pinfunction "1_1") (pintype "passive"))
      (node (ref "C49") (pin "+") (pinfunction "+_+") (pintype "passive"))
      (node (ref "C5") (pin "1") (pinfunction "1_1") (pintype "passive"))
      (node (ref "C6") (pin "1") (pinfunction "1_1") (pintype "passive"))
      (node (ref "C7") (pin "1") (pinfunction "1_1") (pintype "passive"))
      (node (ref "D6") (pin "C") (pinfunction "C_C") (pintype "passive"))
      (node (ref "LED1") (pin "1") (pinfunction "A_1") (pintype "passive"))
      (node (ref "Q1") (pin "2") (pinfunction "D_2") (pintype "bidirectional"))
      (node (ref "VIN_TEST") (pin "1") (pinfunction "1_1") (pintype "passive"))
    )
    (net (code "33") (name "unconnected-(5V_BUCK-POWER_GOOD-Pad5)") (class "Default")
      (node (ref "5V_BUCK") (pin "5") (pinfunction "POWER_GOOD_5") (pintype "bidirectional"))
    )
    (net (code "34") (name "unconnected-(12V_BUCK-POWER_GOOD-Pad5)") (class "Default")
      (node (ref "12V_BUCK") (pin "5") (pinfunction "POWER_GOOD_5") (pintype "bidirectional"))
    )
    (net (code "35") (name "unconnected-(IC1-BALANCE-Pad5)") (class "Default")
      (node (ref "IC1") (pin "5") (pinfunction "BALANCE_5") (pintype "bidirectional"))
    )
  )
)
